# 8_-OUTPUTS.net
KiCad netlist of a schematic drawn in Altium Designer
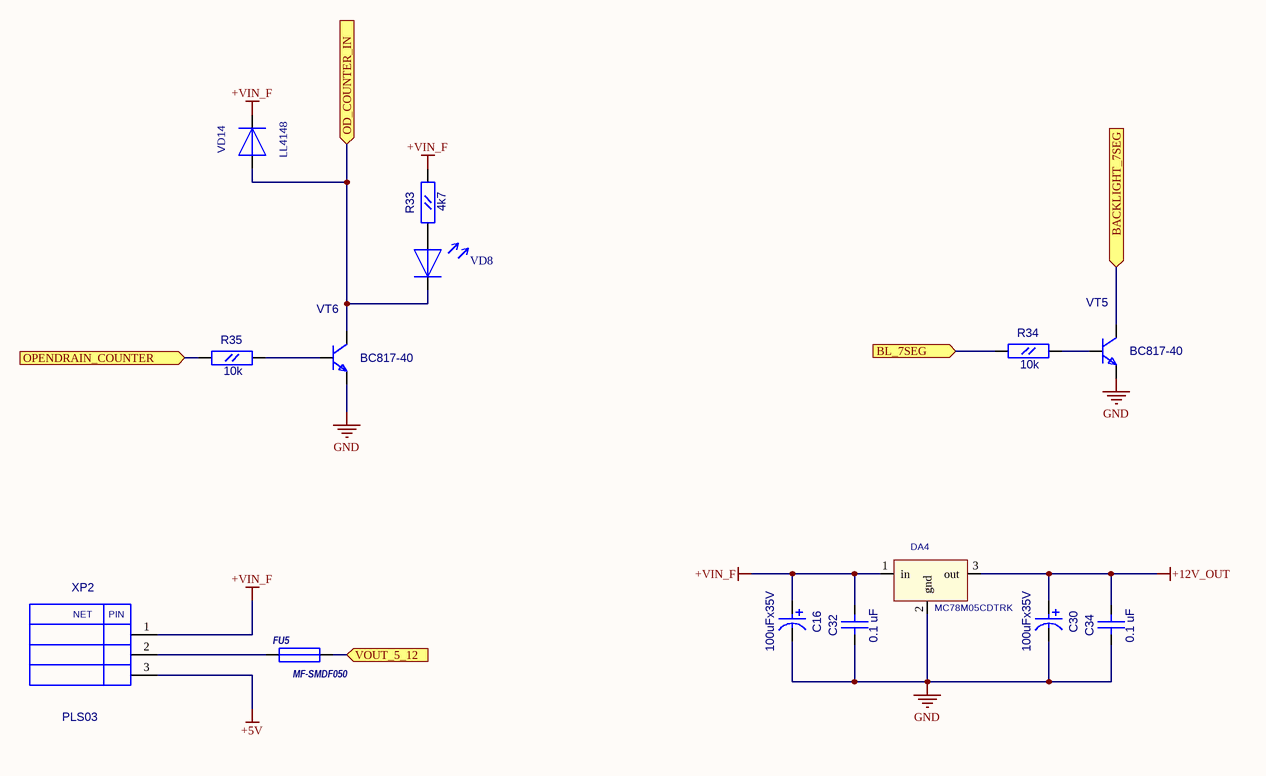
[diagram p0: [8]-OUTPUTS.SchDoc]

(export (version "E")
  (design (tool "Eeschema 10.0.6"))
  (components
    (comp (ref "C16")
      (value "100uFx35V")
      (footprint "CC8X3.5")
      (description "Radial capacitor")
      (libsource (lib "fizik_lib") (part "CAP_8mm"))
    )
    (comp (ref "C30")
      (value "100uFx35V")
      (footprint "CC8X3.5")
      (description "Radial capacitor")
      (libsource (lib "fizik_lib") (part "CAP_8mm"))
    )
    (comp (ref "C32")
      (value "0.1 uF")
      (footprint "CC0603")
      (description "CC0603")
      (libsource (lib "gprs_modem_2") (part "CC0603"))
    )
    (comp (ref "C34")
      (value "0.1 uF")
      (footprint "CC0603")
      (description "CC0603")
      (libsource (lib "gprs_modem_2") (part "CC0603"))
    )
    (comp (ref "DA4")
      (value "MC78M05CDTRK")
      (footprint "D-PAK(TO-252AA)")
      (description "MC78M12CDTRK")
      (libsource (lib "fizik_lib") (part "MC78M05CDTRK"))
    )
    (comp (ref "FU5")
      (value "MF-SMDF050")
      (footprint "MF-SMDF")
      (description "MF-SMDF")
      (libsource (lib "fizik_lib") (part "MF-SMDF"))
    )
    (comp (ref "R33")
      (value "4k7")
      (footprint "RC0603")
      (description "RC0603")
      (libsource (lib "fizik_lib") (part "RC0603"))
    )
    (comp (ref "R34")
      (value "10k")
      (footprint "RC0603")
      (description "RC0603")
      (libsource (lib "fizik_lib") (part "RC0603"))
    )
    (comp (ref "R35")
      (value "10k")
      (footprint "RC0603")
      (description "RC0603")
      (libsource (lib "fizik_lib") (part "RC0603"))
    )
    (comp (ref "VD8")
      (value "LED_0805")
      (footprint "LED0805")
      (libsource (lib "fizik_lib") (part "LED_0805"))
    )
    (comp (ref "VD14") (value "LL4148") (footprint "SOD-80") (libsource (lib "fizik_lib") (part "LL4148")))
    (comp (ref "VT5")
      (value "BC817-40")
      (footprint "SOT-23(123)")
      (description "NPN 500ma transistor")
      (libsource (lib "fizik_lib") (part "BC846BLT1"))
    )
    (comp (ref "VT6")
      (value "BC817-40")
      (footprint "SOT-23(123)")
      (description "NPN 500ma transistor")
      (libsource (lib "fizik_lib") (part "BC846BLT1"))
    )
    (comp (ref "XP2") (value "PLS03") (footprint "PLS-03") (libsource (lib "fizik_lib") (part "PLS03")))
  )
  (nets
    (net (code "1") (name "+5V") (class "Default")
      (node (ref "XP2") (pin "3") (pinfunction "3_3") (pintype "passive"))
    )
    (net (code "2") (name "+12V_OUT") (class "Default")
      (node (ref "C30") (pin "1") (pintype "passive"))
      (node (ref "C34") (pin "1") (pinfunction "A_1") (pintype "passive"))
      (node (ref "DA4") (pin "3") (pinfunction "out_3") (pintype "passive"))
    )
    (net (code "3") (name "+VIN_F") (class "Default")
      (node (ref "C16") (pin "1") (pintype "passive"))
      (node (ref "C32") (pin "1") (pinfunction "A_1") (pintype "passive"))
      (node (ref "DA4") (pin "1") (pinfunction "in_1") (pintype "passive"))
      (node (ref "R33") (pin "2") (pinfunction "B_2") (pintype "passive"))
      (node (ref "VD14") (pin "2") (pinfunction "+_2") (pintype "passive"))
      (node (ref "XP2") (pin "1") (pinfunction "1_1") (pintype "passive"))
    )
    (net (code "4") (name "/BACKLIGHT_7SEG") (class "Default")
      (node (ref "VT5") (pin "3") (pinfunction "C_3") (pintype "passive"))
    )
    (net (code "5") (name "/BL_7SEG") (class "Default")
      (node (ref "R34") (pin "1") (pinfunction "A_1") (pintype "passive"))
    )
    (net (code "6") (name "/OD_COUNTER_IN") (class "Default")
      (node (ref "VD14") (pin "1") (pinfunction "-_1") (pintype "passive"))
      (node (ref "VD8") (pin "2") (pintype "passive"))
      (node (ref "VT6") (pin "3") (pinfunction "C_3") (pintype "passive"))
    )
    (net (code "7") (name "/OPENDRAIN_COUNTER") (class "Default")
      (node (ref "R35") (pin "1") (pinfunction "A_1") (pintype "passive"))
    )
    (net (code "8") (name "/VOUT_5_12") (class "Default") (node (ref "FU5") (pin "2") (pintype "passive")))
    (net (code "9") (name "GND") (class "Default")
      (node (ref "C16") (pin "2") (pintype "passive"))
      (node (ref "C30") (pin "2") (pintype "passive"))
      (node (ref "C32") (pin "2") (pinfunction "B_2") (pintype "passive"))
      (node (ref "C34") (pin "2") (pinfunction "B_2") (pintype "passive"))
      (node (ref "DA4") (pin "2") (pinfunction "gnd_2") (pintype "passive"))
      (node (ref "VT5") (pin "2") (pinfunction "E_2") (pintype "passive"))
      (node (ref "VT6") (pin "2") (pinfunction "E_2") (pintype "passive"))
    )
    (net (code "10") (name "Net-(FU5-Pad1)") (class "Default")
      (node (ref "FU5") (pin "1") (pintype "passive"))
      (node (ref "XP2") (pin "2") (pinfunction "2_2") (pintype "passive"))
    )
    (net (code "11") (name "Net-(R33-A)") (class "Default")
      (node (ref "R33") (pin "1") (pinfunction "A_1") (pintype "passive"))
      (node (ref "VD8") (pin "1") (pintype "passive"))
    )
    (net (code "12") (name "Net-(R34-B)") (class "Default")
      (node (ref "R34") (pin "2") (pinfunction "B_2") (pintype "passive"))
      (node (ref "VT5") (pin "1") (pinfunction "B_1") (pintype "passive"))
    )
    (net (code "13") (name "Net-(R35-B)") (class "Default")
      (node (ref "R35") (pin "2") (pinfunction "B_2") (pintype "passive"))
      (node (ref "VT6") (pin "1") (pinfunction "B_1") (pintype "passive"))
    )
  )
)
